# 02-AXP2101.net
KiCad netlist of a schematic drawn in EasyEDA
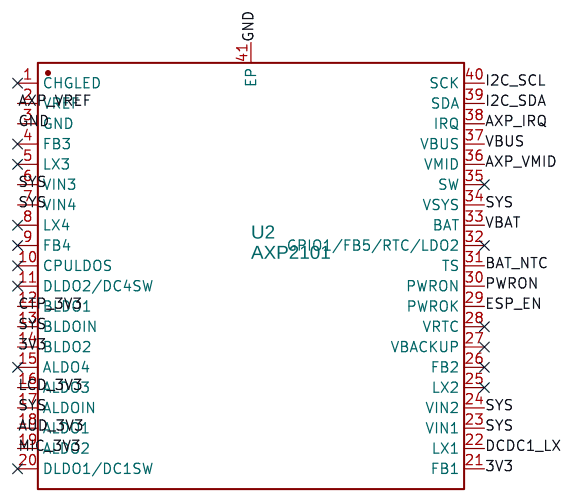
[diagram p0: schematic sheet]

(export (version "E")
  (design (tool "Eeschema 10.0.6"))
  (components
    (comp (ref "U2")
      (value "AXP2101")
      (fields (field (name "Manufacturer") "x-powers()"))
      (libsource (lib "") (part "Unknown_400.0_300.0"))
    )
  )
  (nets
    (net (code "1") (name "/3V3") (class "Default")
      (node (ref "U2") (pin "14") (pinfunction "BLDO2_14") (pintype "unspecified"))
      (node (ref "U2") (pin "21") (pinfunction "FB1_21") (pintype "unspecified"))
    )
    (net (code "2") (name "/AUD_3V3") (class "Default")
      (node (ref "U2") (pin "18") (pinfunction "ALDO1_18") (pintype "unspecified"))
    )
    (net (code "3") (name "/AXP_IRQ") (class "Default")
      (node (ref "U2") (pin "38") (pinfunction "IRQ_38") (pintype "unspecified"))
    )
    (net (code "4") (name "/AXP_VMID") (class "Default")
      (node (ref "U2") (pin "36") (pinfunction "VMID_36") (pintype "unspecified"))
    )
    (net (code "5") (name "/AXP_VREF") (class "Default")
      (node (ref "U2") (pin "2") (pinfunction "VREF_2") (pintype "unspecified"))
    )
    (net (code "6") (name "/BAT_NTC") (class "Default")
      (node (ref "U2") (pin "31") (pinfunction "TS_31") (pintype "unspecified"))
    )
    (net (code "7") (name "/CTP_3V3") (class "Default")
      (node (ref "U2") (pin "12") (pinfunction "BLDO1_12") (pintype "unspecified"))
    )
    (net (code "8") (name "/DCDC1_LX") (class "Default")
      (node (ref "U2") (pin "22") (pinfunction "LX1_22") (pintype "unspecified"))
    )
    (net (code "9") (name "/ESP_EN") (class "Default")
      (node (ref "U2") (pin "29") (pinfunction "PWROK_29") (pintype "unspecified"))
    )
    (net (code "10") (name "/GND") (class "Default")
      (node (ref "U2") (pin "3") (pinfunction "GND_3") (pintype "unspecified"))
      (node (ref "U2") (pin "41") (pinfunction "EP_41") (pintype "unspecified"))
    )
    (net (code "11") (name "/I2C_SCL") (class "Default")
      (node (ref "U2") (pin "40") (pinfunction "SCK_40") (pintype "unspecified"))
    )
    (net (code "12") (name "/I2C_SDA") (class "Default")
      (node (ref "U2") (pin "39") (pinfunction "SDA_39") (pintype "unspecified"))
    )
    (net (code "13") (name "/LCD_3V3") (class "Default")
      (node (ref "U2") (pin "16") (pinfunction "ALDO3_16") (pintype "unspecified"))
    )
    (net (code "14") (name "/MIC_3V3") (class "Default")
      (node (ref "U2") (pin "19") (pinfunction "ALDO2_19") (pintype "unspecified"))
    )
    (net (code "15") (name "/PWRON") (class "Default")
      (node (ref "U2") (pin "30") (pinfunction "PWRON_30") (pintype "unspecified"))
    )
    (net (code "16") (name "/SYS") (class "Default")
      (node (ref "U2") (pin "13") (pinfunction "BLDOIN_13") (pintype "unspecified"))
      (node (ref "U2") (pin "17") (pinfunction "ALDOIN_17") (pintype "unspecified"))
      (node (ref "U2") (pin "23") (pinfunction "VIN1_23") (pintype "unspecified"))
      (node (ref "U2") (pin "24") (pinfunction "VIN2_24") (pintype "unspecified"))
      (node (ref "U2") (pin "34") (pinfunction "VSYS_34") (pintype "unspecified"))
      (node (ref "U2") (pin "6") (pinfunction "VIN3_6") (pintype "unspecified"))
      (node (ref "U2") (pin "7") (pinfunction "VIN4_7") (pintype "unspecified"))
    )
    (net (code "17") (name "/VBAT") (class "Default")
      (node (ref "U2") (pin "33") (pinfunction "BAT_33") (pintype "unspecified"))
    )
    (net (code "18") (name "/VBUS") (class "Default")
      (node (ref "U2") (pin "37") (pinfunction "VBUS_37") (pintype "unspecified"))
    )
    (net (code "19") (name "unconnected-(U2-ALDO4-Pad15)") (class "Default")
      (node (ref "U2") (pin "15") (pinfunction "ALDO4_15") (pintype "unspecified+no_connect"))
    )
    (net (code "20") (name "unconnected-(U2-CHGLED-Pad1)") (class "Default")
      (node (ref "U2") (pin "1") (pinfunction "CHGLED_1") (pintype "unspecified+no_connect"))
    )
    (net (code "21") (name "unconnected-(U2-CPULDOS-Pad10)") (class "Default")
      (node (ref "U2") (pin "10") (pinfunction "CPULDOS_10") (pintype "unspecified+no_connect"))
    )
    (net (code "22") (name "unconnected-(U2-DLDO1{slash}DC1SW-Pad20)") (class "Default")
      (node (ref "U2") (pin "20") (pinfunction "DLDO1/DC1SW_20") (pintype "unspecified+no_connect"))
    )
    (net (code "23") (name "unconnected-(U2-DLDO2{slash}DC4SW-Pad11)") (class "Default")
      (node (ref "U2") (pin "11") (pinfunction "DLDO2/DC4SW_11") (pintype "unspecified+no_connect"))
    )
    (net (code "24") (name "unconnected-(U2-FB2-Pad26)") (class "Default")
      (node (ref "U2") (pin "26") (pinfunction "FB2_26") (pintype "unspecified+no_connect"))
    )
    (net (code "25") (name "unconnected-(U2-FB3-Pad4)") (class "Default")
      (node (ref "U2") (pin "4") (pinfunction "FB3_4") (pintype "unspecified+no_connect"))
    )
    (net (code "26") (name "unconnected-(U2-FB4-Pad9)") (class "Default")
      (node (ref "U2") (pin "9") (pinfunction "FB4_9") (pintype "unspecified+no_connect"))
    )
    (net (code "27") (name "unconnected-(U2-GPIO1{slash}FB5{slash}RTC{slash}LDO2-Pad32)") (class "Default")
      (node (ref "U2") (pin "32") (pinfunction "GPIO1/FB5/RTC/LDO2_32") (pintype "unspecified+no_connect"))
    )
    (net (code "28") (name "unconnected-(U2-LX2-Pad25)") (class "Default")
      (node (ref "U2") (pin "25") (pinfunction "LX2_25") (pintype "unspecified+no_connect"))
    )
    (net (code "29") (name "unconnected-(U2-LX3-Pad5)") (class "Default")
      (node (ref "U2") (pin "5") (pinfunction "LX3_5") (pintype "unspecified+no_connect"))
    )
    (net (code "30") (name "unconnected-(U2-LX4-Pad8)") (class "Default")
      (node (ref "U2") (pin "8") (pinfunction "LX4_8") (pintype "unspecified+no_connect"))
    )
    (net (code "31") (name "unconnected-(U2-SW-Pad35)") (class "Default")
      (node (ref "U2") (pin "35") (pinfunction "SW_35") (pintype "unspecified+no_connect"))
    )
    (net (code "32") (name "unconnected-(U2-VBACKUP-Pad27)") (class "Default")
      (node (ref "U2") (pin "27") (pinfunction "VBACKUP_27") (pintype "unspecified+no_connect"))
    )
    (net (code "33") (name "unconnected-(U2-VRTC-Pad28)") (class "Default")
      (node (ref "U2") (pin "28") (pinfunction "VRTC_28") (pintype "unspecified+no_connect"))
    )
  )
)
